# BoostConverter.net
KiCad netlist of a schematic drawn in Altium Designer
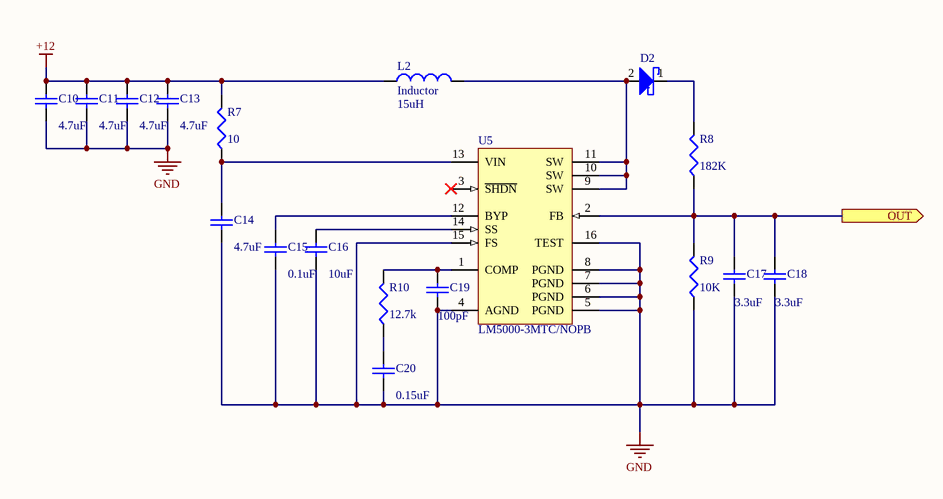
[diagram p0: BoostConverter.SchDoc]

(export (version "E")
  (design (tool "Eeschema 10.0.6"))
  (components
    (comp (ref "C10")
      (value "Cap")
      (footprint "C0805")
      (description "Capacitor")
      (fields (field (name "ALTIUM_UNNAMED_1") "4.7uF") (field (name "PUBLISHER") "Altium Limited"))
      (libsource (lib "Miscellaneous Devices") (part "Cap"))
    )
    (comp (ref "C11")
      (value "Cap")
      (footprint "C0805")
      (description "Capacitor")
      (fields (field (name "ALTIUM_UNNAMED_1") "4.7uF") (field (name "PUBLISHER") "Altium Limited"))
      (libsource (lib "Miscellaneous Devices") (part "Cap"))
    )
    (comp (ref "C12")
      (value "Cap")
      (footprint "C0805")
      (description "Capacitor")
      (fields (field (name "ALTIUM_UNNAMED_1") "4.7uF") (field (name "PUBLISHER") "Altium Limited"))
      (libsource (lib "Miscellaneous Devices") (part "Cap"))
    )
    (comp (ref "C13")
      (value "Cap")
      (footprint "C0805")
      (description "Capacitor")
      (fields (field (name "ALTIUM_UNNAMED_1") "4.7uF") (field (name "PUBLISHER") "Altium Limited"))
      (libsource (lib "Miscellaneous Devices") (part "Cap"))
    )
    (comp (ref "C14")
      (value "Cap")
      (footprint "C0805")
      (description "Capacitor")
      (fields (field (name "ALTIUM_UNNAMED_1") "4.7uF") (field (name "PUBLISHER") "Altium Limited"))
      (libsource (lib "Miscellaneous Devices") (part "Cap"))
    )
    (comp (ref "C15")
      (value "Cap")
      (footprint "C0805")
      (description "Capacitor")
      (fields (field (name "ALTIUM_UNNAMED_1") "0.1uF") (field (name "PUBLISHER") "Altium Limited"))
      (libsource (lib "Miscellaneous Devices") (part "Cap"))
    )
    (comp (ref "C16")
      (value "Cap")
      (footprint "C0805")
      (description "Capacitor")
      (fields (field (name "ALTIUM_UNNAMED_1") "10uF") (field (name "PUBLISHER") "Altium Limited"))
      (libsource (lib "Miscellaneous Devices") (part "Cap"))
    )
    (comp (ref "C17")
      (value "Cap")
      (footprint "C0805")
      (description "Capacitor")
      (fields (field (name "ALTIUM_UNNAMED_1") "3.3uF") (field (name "PUBLISHER") "Altium Limited"))
      (libsource (lib "Miscellaneous Devices") (part "Cap"))
    )
    (comp (ref "C18")
      (value "Cap")
      (footprint "C0805")
      (description "Capacitor")
      (fields (field (name "ALTIUM_UNNAMED_1") "3.3uF") (field (name "PUBLISHER") "Altium Limited"))
      (libsource (lib "Miscellaneous Devices") (part "Cap"))
    )
    (comp (ref "C19")
      (value "Cap")
      (footprint "C0805")
      (description "Capacitor")
      (fields (field (name "ALTIUM_UNNAMED_1") "100pF") (field (name "PUBLISHER") "Altium Limited"))
      (libsource (lib "Miscellaneous Devices") (part "Cap"))
    )
    (comp (ref "C20")
      (value "Cap")
      (footprint "C0805")
      (description "Capacitor")
      (fields (field (name "ALTIUM_UNNAMED_1") "0.15uF") (field (name "PUBLISHER") "Altium Limited"))
      (libsource (lib "Miscellaneous Devices") (part "Cap"))
    )
    (comp (ref "D2")
      (value "Schottky Diode")
      (footprint "DIOM4326X24N")
      (libsource (lib "IntLibrary") (part "B160-13-F"))
    )
    (comp (ref "L2")
      (value "Inductor")
      (footprint "INDC4532")
      (fields (field (name "ALTIUM_VALUE") "15uH") (field (name "PUBLISHER") "Altium Limited"))
      (libsource (lib "Miscellaneous Devices") (part "Inductor"))
    )
    (comp (ref "R7")
      (value "10")
      (footprint "J1-0603")
      (description "Resistor")
      (fields (field (name "Comment") "Res3") (field (name "PUBLISHER") "Altium Limited"))
      (libsource (lib "Miscellaneous Devices") (part "Res3"))
    )
    (comp (ref "R8")
      (value "182K")
      (footprint "J1-0603")
      (description "Resistor")
      (fields (field (name "Comment") "Res3") (field (name "PUBLISHER") "Altium Limited"))
      (libsource (lib "Miscellaneous Devices") (part "Res3"))
    )
    (comp (ref "R9")
      (value "10K")
      (footprint "J1-0603")
      (description "Resistor")
      (fields (field (name "Comment") "Res3") (field (name "PUBLISHER") "Altium Limited"))
      (libsource (lib "Miscellaneous Devices") (part "Res3"))
    )
    (comp (ref "R10")
      (value "12.7k")
      (footprint "6-0805_L")
      (description "Resistor")
      (fields (field (name "Comment") "Res3") (field (name "PUBLISHER") "Altium Limited"))
      (libsource (lib "Miscellaneous Devices") (part "Res3"))
    )
    (comp (ref "U5")
      (value "LM5000-3MTC/NOPB")
      (footprint "PW0016A_L")
      (description "High Voltage Switch Mode Regulator, 16-pin TSSOP, Pb-Free")
      (fields (field (name "MANUFACTURER") "Texas Instruments"))
      (libsource (lib "Altium Content Vault") (part "PM-SMPS-LM5000-16"))
    )
  )
  (nets
    (net (code "1") (name "+12") (class "Default")
      (node (ref "C10") (pin "2") (pinfunction "2_2") (pintype "passive"))
      (node (ref "C11") (pin "2") (pinfunction "2_2") (pintype "passive"))
      (node (ref "C12") (pin "2") (pinfunction "2_2") (pintype "passive"))
      (node (ref "C13") (pin "2") (pinfunction "2_2") (pintype "passive"))
      (node (ref "L2") (pin "1") (pinfunction "1_1") (pintype "passive"))
      (node (ref "R7") (pin "2") (pinfunction "2_2") (pintype "passive"))
    )
    (net (code "2") (name "/OUT") (class "Default")
      (node (ref "C17") (pin "2") (pinfunction "2_2") (pintype "passive"))
      (node (ref "C18") (pin "2") (pinfunction "2_2") (pintype "passive"))
      (node (ref "R8") (pin "1") (pinfunction "1_1") (pintype "passive"))
      (node (ref "R9") (pin "2") (pinfunction "2_2") (pintype "passive"))
      (node (ref "U5") (pin "2") (pinfunction "FB_2") (pintype "input"))
    )
    (net (code "3") (name "GND") (class "Default")
      (node (ref "C10") (pin "1") (pinfunction "1_1") (pintype "passive"))
      (node (ref "C11") (pin "1") (pinfunction "1_1") (pintype "passive"))
      (node (ref "C12") (pin "1") (pinfunction "1_1") (pintype "passive"))
      (node (ref "C13") (pin "1") (pinfunction "1_1") (pintype "passive"))
      (node (ref "C14") (pin "1") (pinfunction "1_1") (pintype "passive"))
      (node (ref "C15") (pin "1") (pinfunction "1_1") (pintype "passive"))
      (node (ref "C16") (pin "1") (pinfunction "1_1") (pintype "passive"))
      (node (ref "C17") (pin "1") (pinfunction "1_1") (pintype "passive"))
      (node (ref "C18") (pin "1") (pinfunction "1_1") (pintype "passive"))
      (node (ref "C19") (pin "1") (pinfunction "1_1") (pintype "passive"))
      (node (ref "C20") (pin "1") (pinfunction "1_1") (pintype "passive"))
      (node (ref "R9") (pin "1") (pinfunction "1_1") (pintype "passive"))
      (node (ref "U5") (pin "15") (pinfunction "FS_15") (pintype "input"))
      (node (ref "U5") (pin "16") (pinfunction "TEST_16") (pintype "passive"))
      (node (ref "U5") (pin "4") (pinfunction "AGND_4") (pintype "power_in"))
      (node (ref "U5") (pin "5") (pinfunction "PGND_5") (pintype "power_in"))
      (node (ref "U5") (pin "6") (pinfunction "PGND_6") (pintype "power_in"))
      (node (ref "U5") (pin "7") (pinfunction "PGND_7") (pintype "power_in"))
      (node (ref "U5") (pin "8") (pinfunction "PGND_8") (pintype "power_in"))
    )
    (net (code "4") (name "Net-(C20-Pad2)") (class "Default")
      (node (ref "C20") (pin "2") (pinfunction "2_2") (pintype "passive"))
      (node (ref "R10") (pin "1") (pinfunction "1_1") (pintype "passive"))
    )
    (net (code "5") (name "Net-(D2-Pad1)") (class "Default")
      (node (ref "D2") (pin "1") (pinfunction "1_1") (pintype "passive"))
      (node (ref "R8") (pin "2") (pinfunction "2_2") (pintype "passive"))
    )
    (net (code "6") (name "Net-(D2-Pad2)") (class "Default")
      (node (ref "D2") (pin "2") (pinfunction "2_2") (pintype "passive"))
      (node (ref "L2") (pin "2") (pinfunction "2_2") (pintype "passive"))
      (node (ref "U5") (pin "10") (pinfunction "SW_10") (pintype "power_in"))
      (node (ref "U5") (pin "11") (pinfunction "SW_11") (pintype "power_in"))
      (node (ref "U5") (pin "9") (pinfunction "SW_9") (pintype "power_in"))
    )
    (net (code "7") (name "Net-(U5-BYP)") (class "Default")
      (node (ref "C15") (pin "2") (pinfunction "2_2") (pintype "passive"))
      (node (ref "U5") (pin "12") (pinfunction "BYP_12") (pintype "passive"))
    )
    (net (code "8") (name "Net-(U5-COMP)") (class "Default")
      (node (ref "C19") (pin "2") (pinfunction "2_2") (pintype "passive"))
      (node (ref "R10") (pin "2") (pinfunction "2_2") (pintype "passive"))
      (node (ref "U5") (pin "1") (pinfunction "COMP_1") (pintype "passive"))
    )
    (net (code "9") (name "Net-(U5-SS)") (class "Default")
      (node (ref "C16") (pin "2") (pinfunction "2_2") (pintype "passive"))
      (node (ref "U5") (pin "14") (pinfunction "SS_14") (pintype "input"))
    )
    (net (code "10") (name "Net-(U5-VIN)") (class "Default")
      (node (ref "C14") (pin "2") (pinfunction "2_2") (pintype "passive"))
      (node (ref "R7") (pin "1") (pinfunction "1_1") (pintype "passive"))
      (node (ref "U5") (pin "13") (pinfunction "VIN_13") (pintype "power_in"))
    )
    (net (code "11") (name "unconnected-(U5-~{SHDN}-Pad3)") (class "Default")
      (node (ref "U5") (pin "3") (pinfunction "~{SHDN}_3") (pintype "input+no_connect"))
    )
  )
)
